# Hydrogen_Rocket_BK.net
KiCad netlist of a schematic drawn in EasyEDA
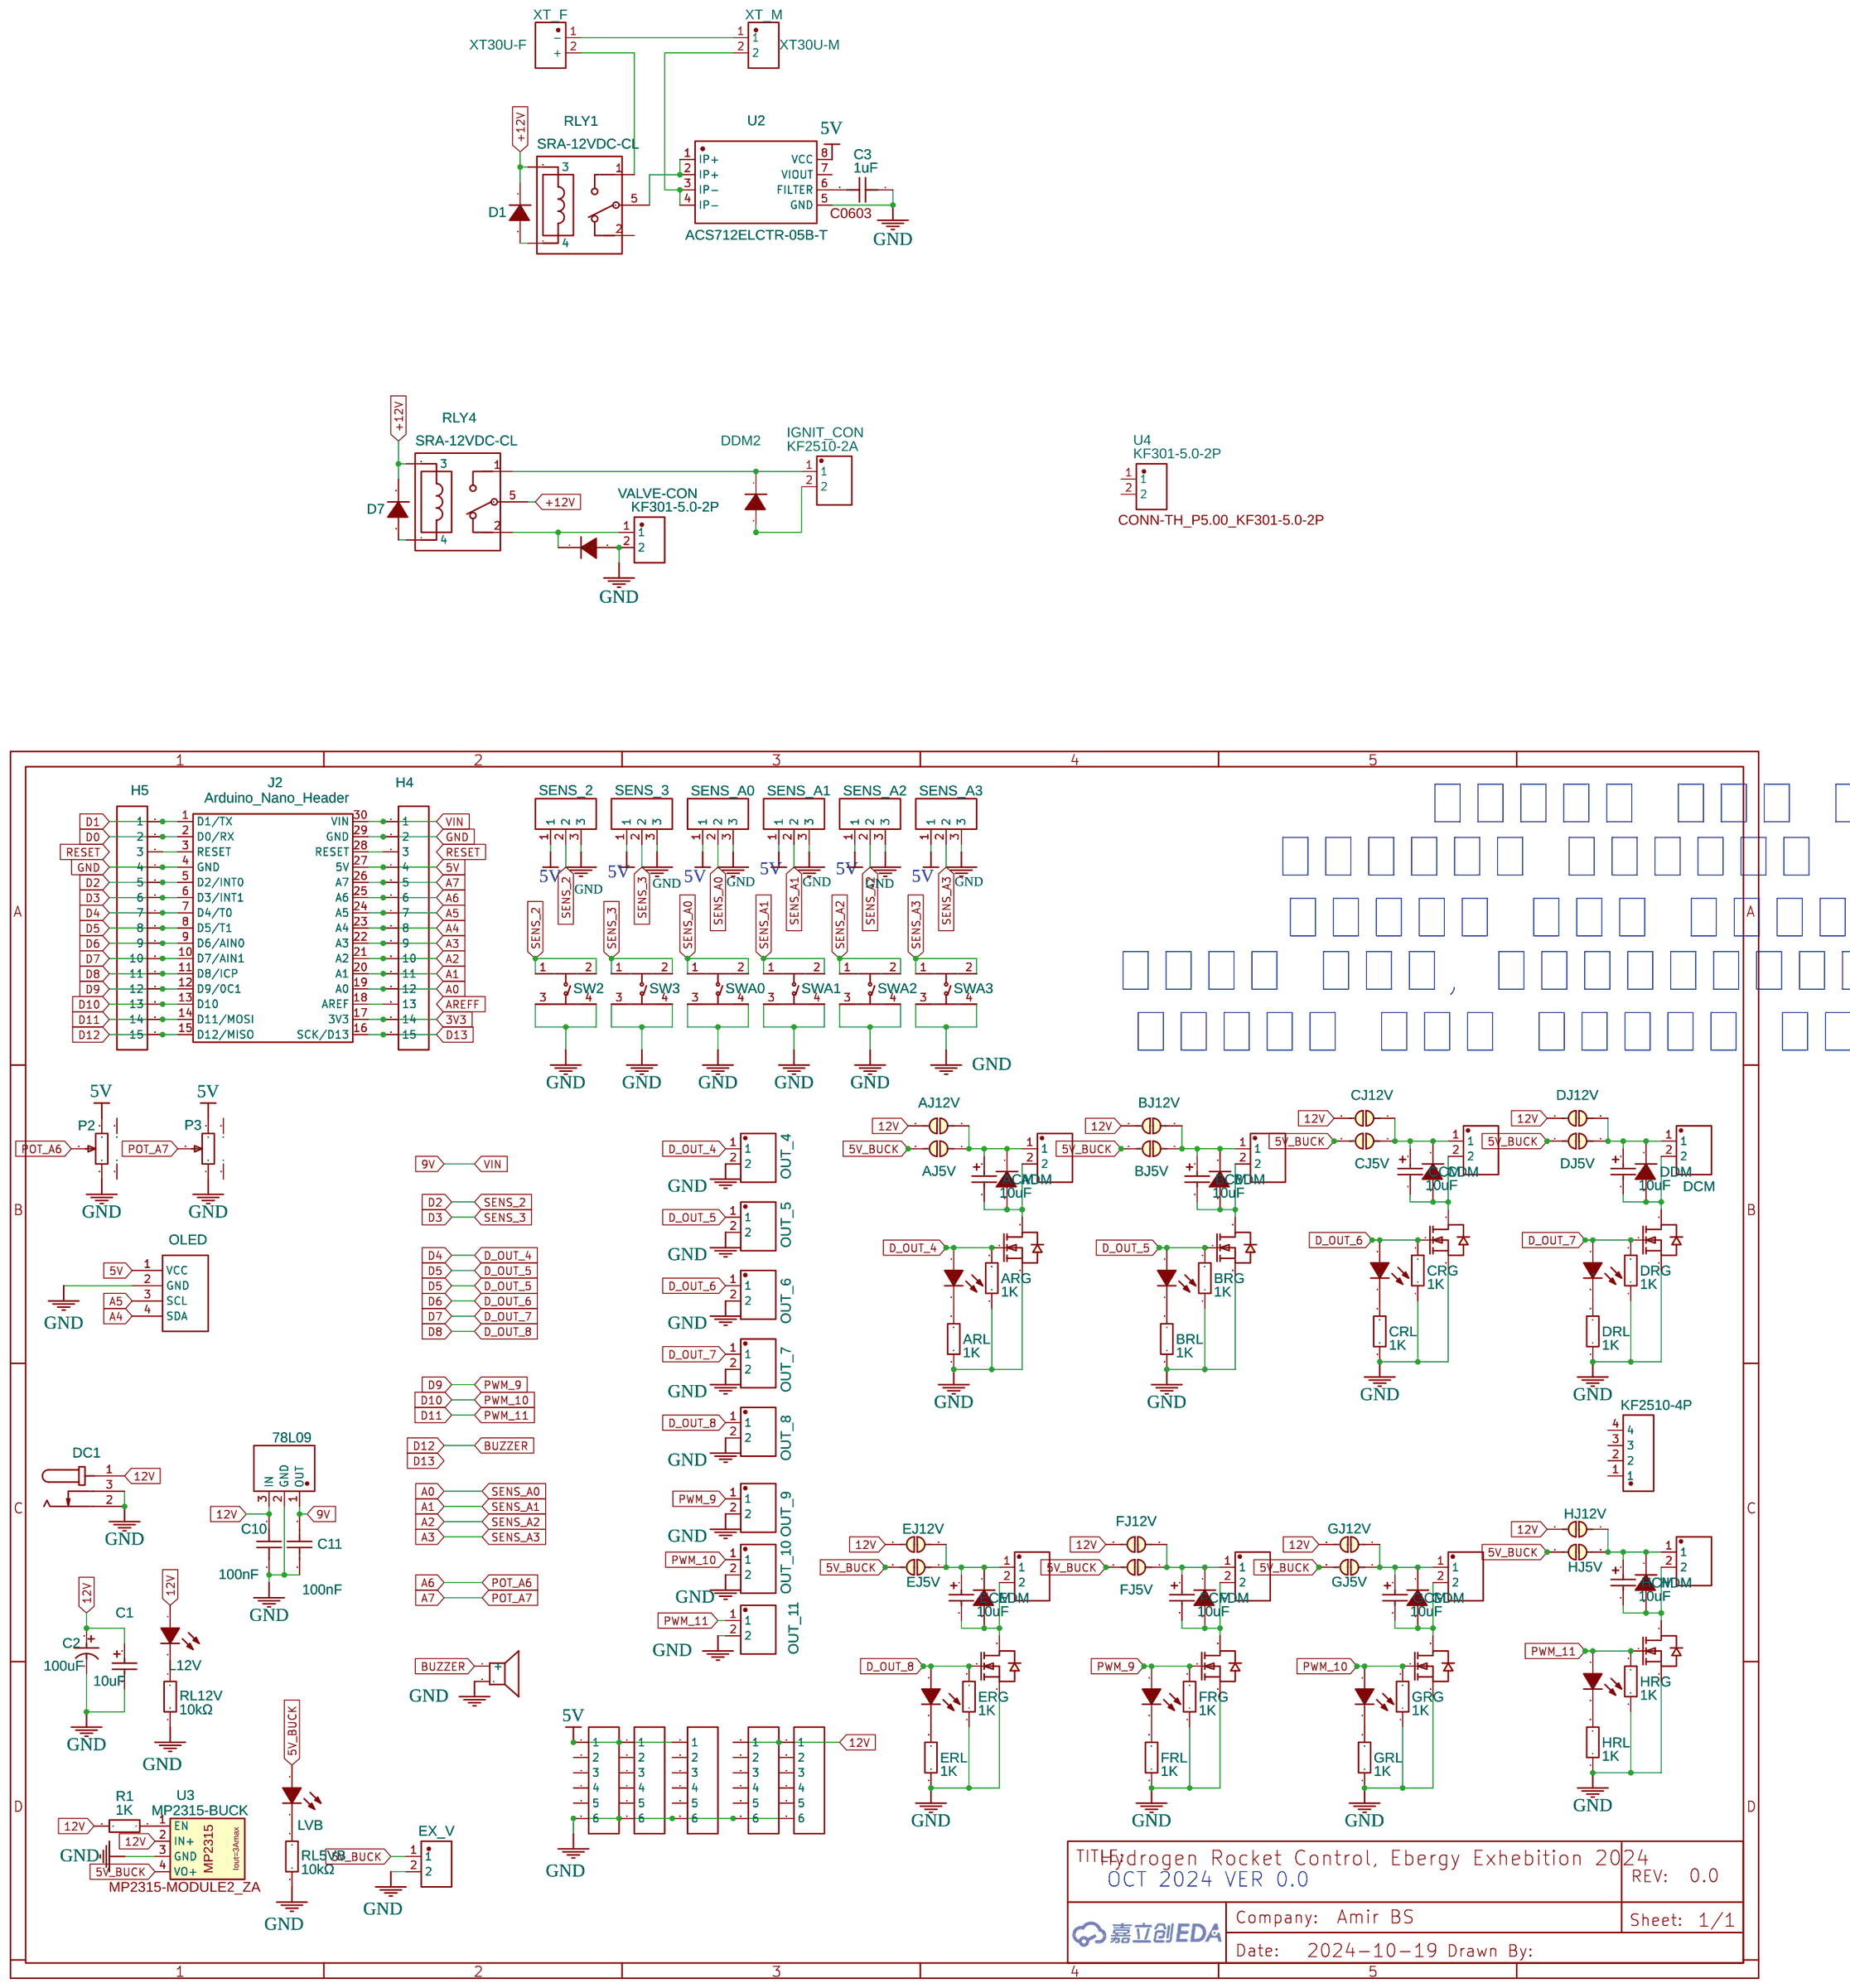
[diagram p0: schematic sheet]

(export (version "E")
  (design (tool "Eeschema 10.0.6"))
  (components
    (comp (ref "ACM")
      (value "10uF")
      (fields (field (name "Manufacturer Part") "TAJA106K016RNJ") (field (name "Manufacturer") "Kyocera AVX"))
      (libsource (lib "") (part "TAJA106K016RNJ_3"))
    )
    (comp (ref "ACON")
      (value "KF2510-2A")
      (fields (field (name "BOM_Supplier Part") "C27543"))
      (libsource (lib "") (part "KF2510-2A_9"))
    )
    (comp (ref "ADM")
      (value "1N4007")
      (fields (field (name "BOM_Manufacturer Part") "1N4007F") (field (name "BOM_Supplier Part") "C110856"))
      (libsource (lib "") (part "1N4007F_3"))
    )
    (comp (ref "AJ5V") (value "JUMPER-SMT_2") (libsource (lib "") (part "JUMPER-SMT_2_13")))
    (comp (ref "AJ12V") (value "JUMPER-SMT_2") (libsource (lib "") (part "JUMPER-SMT_2_6")))
    (comp (ref "ALD")
      (value "LED")
      (fields
        (field (name "BOM_Manufacturer Part") "19-217/BHC-ZL1M2RY/3T")
        (field (name "BOM_Supplier Part") "C72041")
      )
      (libsource (lib "") (part "19-217/BHC-ZL1M2RY/3T_6"))
    )
    (comp (ref "AQ")
      (value "Q")
      (fields (field (name "BOM_Manufacturer Part") "AO3400") (field (name "BOM_Supplier Part") "C5224189"))
      (libsource (lib "") (part "JSM2302"))
    )
    (comp (ref "ARG")
      (value "1K")
      (fields
        (field (name "BOM_Manufacturer Part") "0603WAF1001T5E")
        (field (name "BOM_Supplier Part") "C21190")
      )
      (libsource (lib "") (part "0603WAF1001T5E_7"))
    )
    (comp (ref "ARL")
      (value "1K")
      (fields
        (field (name "BOM_Manufacturer Part") "0603WAF1001T5E")
        (field (name "BOM_Supplier Part") "C21190")
      )
      (libsource (lib "") (part "0603WAF1001T5E_12"))
    )
    (comp (ref "BCM")
      (value "10uF")
      (fields (field (name "Manufacturer Part") "TAJA106K016RNJ") (field (name "Manufacturer") "Kyocera AVX"))
      (libsource (lib "") (part "TAJA106K016RNJ_2"))
    )
    (comp (ref "BCON")
      (value "KF2510-2A")
      (fields (field (name "BOM_Supplier Part") "C27543"))
      (libsource (lib "") (part "KF2510-2A"))
    )
    (comp (ref "BDM")
      (value "1N4007")
      (fields (field (name "BOM_Manufacturer Part") "1N4007F") (field (name "BOM_Supplier Part") "C110856"))
      (libsource (lib "") (part "1N4007F_8"))
    )
    (comp (ref "BJ5V") (value "JUMPER-SMT_2") (libsource (lib "") (part "JUMPER-SMT_2_1")))
    (comp (ref "BJ12V") (value "JUMPER-SMT_2") (libsource (lib "") (part "JUMPER-SMT_2")))
    (comp (ref "BLD")
      (value "LED")
      (fields
        (field (name "BOM_Manufacturer Part") "19-217/BHC-ZL1M2RY/3T")
        (field (name "BOM_Supplier Part") "C72041")
      )
      (libsource (lib "") (part "19-217/BHC-ZL1M2RY/3T_5"))
    )
    (comp (ref "BQ")
      (value "Q")
      (fields (field (name "BOM_Manufacturer Part") "AO3400") (field (name "BOM_Supplier Part") "C5224189"))
      (libsource (lib "") (part "JSM2302_2"))
    )
    (comp (ref "BRG")
      (value "1K")
      (fields
        (field (name "BOM_Manufacturer Part") "0603WAF1001T5E")
        (field (name "BOM_Supplier Part") "C21190")
      )
      (libsource (lib "") (part "0603WAF1001T5E_15"))
    )
    (comp (ref "BRL")
      (value "1K")
      (fields
        (field (name "BOM_Manufacturer Part") "0603WAF1001T5E")
        (field (name "BOM_Supplier Part") "C21190")
      )
      (libsource (lib "") (part "0603WAF1001T5E_11"))
    )
    (comp (ref "BUZZER1")
      (value "BUZZER-12X9")
      (fields (field (name "Manufacturer Part") "buzzer-12X9"))
      (libsource (lib "") (part "BUZZER-12X9"))
    )
    (comp (ref "C1")
      (value "10uF")
      (fields (field (name "Manufacturer Part") "TAJA106K016RNJ") (field (name "Manufacturer") "Kyocera AVX"))
      (libsource (lib "") (part "TAJA106K016RNJ_1"))
    )
    (comp (ref "C2")
      (value "100uF")
      (fields
        (field (name "Manufacturer Part") "KM107M035E11RR0VH2FP0")
        (field (name "Manufacturer") "CX(承兴)")
      )
      (libsource (lib "") (part "100uF 35V 6.3*11"))
    )
    (comp (ref "C3")
      (value "1uF")
      (fields
        (field (name "Manufacturer Part") "CL10A105KB8NNNC")
        (field (name "Manufacturer") "SAMSUNG(三星)")
      )
      (libsource (lib "") (part "CL10A105KB8NNNC"))
    )
    (comp (ref "C10")
      (value "100nF")
      (fields
        (field (name "Manufacturer Part") "CC0603KRX7R9BB104")
        (field (name "Manufacturer") "YAGEO(国巨)")
      )
      (libsource (lib "") (part "CC0603KRX7R9BB104"))
    )
    (comp (ref "C11")
      (value "100nF")
      (fields
        (field (name "Manufacturer Part") "CC0603KRX7R9BB104")
        (field (name "Manufacturer") "YAGEO(国巨)")
      )
      (libsource (lib "") (part "CC0603KRX7R9BB104"))
    )
    (comp (ref "CCM")
      (value "10uF")
      (fields (field (name "Manufacturer Part") "TAJA106K016RNJ") (field (name "Manufacturer") "Kyocera AVX"))
      (libsource (lib "") (part "TAJA106K016RNJ_8"))
    )
    (comp (ref "CCON")
      (value "KF2510-2A")
      (fields (field (name "BOM_Supplier Part") "C27543"))
      (libsource (lib "") (part "KF2510-2A_3"))
    )
    (comp (ref "CDM")
      (value "1N4007")
      (fields (field (name "BOM_Manufacturer Part") "1N4007F") (field (name "BOM_Supplier Part") "C110856"))
      (libsource (lib "") (part "1N4007F_2"))
    )
    (comp (ref "CJ5V") (value "JUMPER-SMT_2") (libsource (lib "") (part "JUMPER-SMT_2_4")))
    (comp (ref "CJ12V") (value "JUMPER-SMT_2") (libsource (lib "") (part "JUMPER-SMT_2_11")))
    (comp (ref "CLD")
      (value "LED")
      (fields
        (field (name "BOM_Manufacturer Part") "19-217/BHC-ZL1M2RY/3T")
        (field (name "BOM_Supplier Part") "C72041")
      )
      (libsource (lib "") (part "19-217/BHC-ZL1M2RY/3T_8"))
    )
    (comp (ref "CQ")
      (value "Q")
      (fields (field (name "BOM_Manufacturer Part") "AO3400") (field (name "BOM_Supplier Part") "C5224189"))
      (libsource (lib "") (part "JSM2302_7"))
    )
    (comp (ref "CRG")
      (value "1K")
      (fields
        (field (name "BOM_Manufacturer Part") "0603WAF1001T5E")
        (field (name "BOM_Supplier Part") "C21190")
      )
      (libsource (lib "") (part "0603WAF1001T5E"))
    )
    (comp (ref "CRL")
      (value "1K")
      (fields
        (field (name "BOM_Manufacturer Part") "0603WAF1001T5E")
        (field (name "BOM_Supplier Part") "C21190")
      )
      (libsource (lib "") (part "0603WAF1001T5E_8"))
    )
    (comp (ref "D1")
      (value "M7_C95872")
      (fields (field (name "Manufacturer Part") "M7") (field (name "Manufacturer") "MDD"))
      (libsource (lib "") (part "M7_C95872"))
    )
    (comp (ref "D7")
      (value "M7_C95872")
      (fields (field (name "Manufacturer Part") "M7") (field (name "Manufacturer") "MDD"))
      (libsource (lib "") (part "M7_C95872"))
    )
    (comp (ref "DC1")
      (value "DC")
      (fields
        (field (name "BOM_Manufacturer Part") "DC005-2.0MM")
        (field (name "BOM_Supplier Part") "C111567")
      )
      (libsource (lib "") (part "DC005-2.0MM"))
    )
    (comp (ref "DCM")
      (value "10uF")
      (fields (field (name "Manufacturer Part") "TAJA106K016RNJ") (field (name "Manufacturer") "Kyocera AVX"))
      (libsource (lib "") (part "TAJA106K016RNJ_5"))
    )
    (comp (ref "DCON")
      (value "KF2510-2A")
      (fields (field (name "BOM_Supplier Part") "C27543"))
      (libsource (lib "") (part "KF2510-2A_2"))
    )
    (comp (ref "DDM")
      (value "1N4007")
      (fields (field (name "BOM_Manufacturer Part") "1N4007F") (field (name "BOM_Supplier Part") "C110856"))
      (libsource (lib "") (part "1N4007F_6"))
    )
    (comp (ref "DDM1")
      (value "1N4007")
      (fields (field (name "BOM_Manufacturer Part") "1N4007F") (field (name "BOM_Supplier Part") "C110856"))
      (libsource (lib "") (part "1N4007F_1"))
    )
    (comp (ref "DDM2")
      (value "1N4007")
      (fields (field (name "BOM_Manufacturer Part") "1N4007F") (field (name "BOM_Supplier Part") "C110856"))
      (libsource (lib "") (part "1N4007F_6"))
    )
    (comp (ref "DJ5V") (value "JUMPER-SMT_2") (libsource (lib "") (part "JUMPER-SMT_2_15")))
    (comp (ref "DJ12V") (value "JUMPER-SMT_2") (libsource (lib "") (part "JUMPER-SMT_2_2")))
    (comp (ref "DLD")
      (value "LED")
      (fields
        (field (name "BOM_Manufacturer Part") "19-217/BHC-ZL1M2RY/3T")
        (field (name "BOM_Supplier Part") "C72041")
      )
      (libsource (lib "") (part "19-217/BHC-ZL1M2RY/3T_7"))
    )
    (comp (ref "DQ")
      (value "Q")
      (fields (field (name "BOM_Manufacturer Part") "AO3400") (field (name "BOM_Supplier Part") "C5224189"))
      (libsource (lib "") (part "JSM2302_6"))
    )
    (comp (ref "DRG")
      (value "1K")
      (fields
        (field (name "BOM_Manufacturer Part") "0603WAF1001T5E")
        (field (name "BOM_Supplier Part") "C21190")
      )
      (libsource (lib "") (part "0603WAF1001T5E_4"))
    )
    (comp (ref "DRL")
      (value "1K")
      (fields
        (field (name "BOM_Manufacturer Part") "0603WAF1001T5E")
        (field (name "BOM_Supplier Part") "C21190")
      )
      (libsource (lib "") (part "0603WAF1001T5E_14"))
    )
    (comp (ref "ECM")
      (value "10uF")
      (fields (field (name "Manufacturer Part") "TAJA106K016RNJ") (field (name "Manufacturer") "Kyocera AVX"))
      (libsource (lib "") (part "TAJA106K016RNJ_7"))
    )
    (comp (ref "ECON")
      (value "KF2510-2A")
      (fields (field (name "BOM_Supplier Part") "C27543"))
      (libsource (lib "") (part "KF2510-2A_4"))
    )
    (comp (ref "EDM")
      (value "1N4007")
      (fields (field (name "BOM_Manufacturer Part") "1N4007F") (field (name "BOM_Supplier Part") "C110856"))
      (libsource (lib "") (part "1N4007F"))
    )
    (comp (ref "EJ5V") (value "JUMPER-SMT_2") (libsource (lib "") (part "JUMPER-SMT_2_14")))
    (comp (ref "EJ12V") (value "JUMPER-SMT_2") (libsource (lib "") (part "JUMPER-SMT_2_12")))
    (comp (ref "ELD")
      (value "LED")
      (fields
        (field (name "BOM_Manufacturer Part") "19-217/BHC-ZL1M2RY/3T")
        (field (name "BOM_Supplier Part") "C72041")
      )
      (libsource (lib "") (part "19-217/BHC-ZL1M2RY/3T_3"))
    )
    (comp (ref "EQ")
      (value "Q")
      (fields (field (name "BOM_Manufacturer Part") "AO3400") (field (name "BOM_Supplier Part") "C5224189"))
      (libsource (lib "") (part "JSM2302_4"))
    )
    (comp (ref "ERG")
      (value "1K")
      (fields
        (field (name "BOM_Manufacturer Part") "0603WAF1001T5E")
        (field (name "BOM_Supplier Part") "C21190")
      )
      (libsource (lib "") (part "0603WAF1001T5E_9"))
    )
    (comp (ref "ERL")
      (value "1K")
      (fields
        (field (name "BOM_Manufacturer Part") "0603WAF1001T5E")
        (field (name "BOM_Supplier Part") "C21190")
      )
      (libsource (lib "") (part "0603WAF1001T5E_5"))
    )
    (comp (ref "EX_V")
      (value "EX_V")
      (fields
        (field (name "Manufacturer Part") "WJ306V-5.0-2P-14-00A")
        (field (name "Manufacturer") "KANGNEX(康奈克斯电气)")
      )
      (libsource (lib "") (part "WJ306V-5.0-2P-14-00A"))
    )
    (comp (ref "FCM")
      (value "10uF")
      (fields (field (name "Manufacturer Part") "TAJA106K016RNJ") (field (name "Manufacturer") "Kyocera AVX"))
      (libsource (lib "") (part "TAJA106K016RNJ"))
    )
    (comp (ref "FCON")
      (value "KF2510-2A")
      (fields (field (name "BOM_Supplier Part") "C27543"))
      (libsource (lib "") (part "KF2510-2A_8"))
    )
    (comp (ref "FDM")
      (value "1N4007")
      (fields (field (name "BOM_Manufacturer Part") "1N4007F") (field (name "BOM_Supplier Part") "C110856"))
      (libsource (lib "") (part "1N4007F_4"))
    )
    (comp (ref "FJ5V") (value "JUMPER-SMT_2") (libsource (lib "") (part "JUMPER-SMT_2_5")))
    (comp (ref "FJ12V") (value "JUMPER-SMT_2") (libsource (lib "") (part "JUMPER-SMT_2_10")))
    (comp (ref "FLD")
      (value "LED")
      (fields
        (field (name "BOM_Manufacturer Part") "19-217/BHC-ZL1M2RY/3T")
        (field (name "BOM_Supplier Part") "C72041")
      )
      (libsource (lib "") (part "19-217/BHC-ZL1M2RY/3T"))
    )
    (comp (ref "FQ")
      (value "Q")
      (fields (field (name "BOM_Manufacturer Part") "AO3400") (field (name "BOM_Supplier Part") "C5224189"))
      (libsource (lib "") (part "JSM2302_1"))
    )
    (comp (ref "FRG")
      (value "1K")
      (fields
        (field (name "BOM_Manufacturer Part") "0603WAF1001T5E")
        (field (name "BOM_Supplier Part") "C21190")
      )
      (libsource (lib "") (part "0603WAF1001T5E_10"))
    )
    (comp (ref "FRL")
      (value "1K")
      (fields
        (field (name "BOM_Manufacturer Part") "0603WAF1001T5E")
        (field (name "BOM_Supplier Part") "C21190")
      )
      (libsource (lib "") (part "0603WAF1001T5E_16"))
    )
    (comp (ref "GCM")
      (value "10uF")
      (fields (field (name "Manufacturer Part") "TAJA106K016RNJ") (field (name "Manufacturer") "Kyocera AVX"))
      (libsource (lib "") (part "TAJA106K016RNJ_6"))
    )
    (comp (ref "GCON")
      (value "KF2510-2A")
      (fields (field (name "BOM_Supplier Part") "C27543"))
      (libsource (lib "") (part "KF2510-2A_7"))
    )
    (comp (ref "GDM")
      (value "1N4007")
      (fields (field (name "BOM_Manufacturer Part") "1N4007F") (field (name "BOM_Supplier Part") "C110856"))
      (libsource (lib "") (part "1N4007F_7"))
    )
    (comp (ref "GJ5V") (value "JUMPER-SMT_2") (libsource (lib "") (part "JUMPER-SMT_2_9")))
    (comp (ref "GJ12V") (value "JUMPER-SMT_2") (libsource (lib "") (part "JUMPER-SMT_2_3")))
    (comp (ref "GLD")
      (value "LED")
      (fields
        (field (name "BOM_Manufacturer Part") "19-217/BHC-ZL1M2RY/3T")
        (field (name "BOM_Supplier Part") "C72041")
      )
      (libsource (lib "") (part "19-217/BHC-ZL1M2RY/3T_9"))
    )
    (comp (ref "GQ")
      (value "Q")
      (fields (field (name "BOM_Manufacturer Part") "AO3400") (field (name "BOM_Supplier Part") "C5224189"))
      (libsource (lib "") (part "JSM2302_5"))
    )
    (comp (ref "GRG")
      (value "1K")
      (fields
        (field (name "BOM_Manufacturer Part") "0603WAF1001T5E")
        (field (name "BOM_Supplier Part") "C21190")
      )
      (libsource (lib "") (part "0603WAF1001T5E_3"))
    )
    (comp (ref "GRL")
      (value "1K")
      (fields
        (field (name "BOM_Manufacturer Part") "0603WAF1001T5E")
        (field (name "BOM_Supplier Part") "C21190")
      )
      (libsource (lib "") (part "0603WAF1001T5E_13"))
    )
    (comp (ref "H1")
      (value "HDR-F-2.54_1x6")
      (fields (field (name "BOM_Supplier Part") "C40877"))
      (libsource (lib "") (part "HDR-F-2.54_1x6"))
    )
    (comp (ref "H2")
      (value "HDR-F-2.54_1x6")
      (fields (field (name "BOM_Supplier Part") "C40877"))
      (libsource (lib "") (part "HDR-F-2.54_1x6"))
    )
    (comp (ref "H3")
      (value "HDR-F-2.54_1x6")
      (fields (field (name "BOM_Supplier Part") "C40877"))
      (libsource (lib "") (part "HDR-F-2.54_1x6"))
    )
    (comp (ref "H4")
      (value "HDR-F-2.54_1x15")
      (fields (field (name "BOM_Supplier Part") "C124408"))
      (libsource (lib "") (part "HDR-F-2.54_1x15_1"))
    )
    (comp (ref "H5")
      (value "HDR-F-2.54_1x15")
      (fields (field (name "BOM_Supplier Part") "C124408"))
      (libsource (lib "") (part "HDR-F-2.54_1x15"))
    )
    (comp (ref "H6")
      (value "HDR-F-2.54_1x6")
      (fields (field (name "BOM_Supplier Part") "C40877"))
      (libsource (lib "") (part "HDR-F-2.54_1x6"))
    )
    (comp (ref "H11")
      (value "HDR-F-2.54_1x6")
      (fields (field (name "BOM_Supplier Part") "C40877"))
      (libsource (lib "") (part "HDR-F-2.54_1x6"))
    )
    (comp (ref "HCM")
      (value "10uF")
      (fields (field (name "Manufacturer Part") "TAJA106K016RNJ") (field (name "Manufacturer") "Kyocera AVX"))
      (libsource (lib "") (part "TAJA106K016RNJ_4"))
    )
    (comp (ref "HCON")
      (value "KF2510-2A")
      (fields (field (name "BOM_Supplier Part") "C27543"))
      (libsource (lib "") (part "KF2510-2A_5"))
    )
    (comp (ref "HDM")
      (value "1N4007")
      (fields (field (name "BOM_Manufacturer Part") "1N4007F") (field (name "BOM_Supplier Part") "C110856"))
      (libsource (lib "") (part "1N4007F_5"))
    )
    (comp (ref "HJ5V") (value "JUMPER-SMT_2") (libsource (lib "") (part "JUMPER-SMT_2_7")))
    (comp (ref "HJ12V") (value "JUMPER-SMT_2") (libsource (lib "") (part "JUMPER-SMT_2_8")))
    (comp (ref "HLD")
      (value "LED")
      (fields
        (field (name "BOM_Manufacturer Part") "19-217/BHC-ZL1M2RY/3T")
        (field (name "BOM_Supplier Part") "C72041")
      )
      (libsource (lib "") (part "19-217/BHC-ZL1M2RY/3T_1"))
    )
    (comp (ref "HQ")
      (value "Q")
      (fields (field (name "BOM_Manufacturer Part") "AO3400") (field (name "BOM_Supplier Part") "C5224189"))
      (libsource (lib "") (part "JSM2302_3"))
    )
    (comp (ref "HRG")
      (value "1K")
      (fields
        (field (name "BOM_Manufacturer Part") "0603WAF1001T5E")
        (field (name "BOM_Supplier Part") "C21190")
      )
      (libsource (lib "") (part "0603WAF1001T5E_2"))
    )
    (comp (ref "HRL")
      (value "1K")
      (fields
        (field (name "BOM_Manufacturer Part") "0603WAF1001T5E")
        (field (name "BOM_Supplier Part") "C21190")
      )
      (libsource (lib "") (part "0603WAF1001T5E_1"))
    )
    (comp (ref "IGNIT_CON")
      (value "KF2510-2A")
      (fields (field (name "BOM_Supplier Part") "C27543"))
      (libsource (lib "") (part "KF2510-2A_1"))
    )
    (comp (ref "J2") (value "Arduino_Nano_Header") (libsource (lib "") (part "Arduino_Nano_Header")))
    (comp (ref "L12V")
      (value "LED")
      (fields
        (field (name "BOM_Manufacturer Part") "19-217/BHC-ZL1M2RY/3T")
        (field (name "BOM_Supplier Part") "C72041")
      )
      (libsource (lib "") (part "19-217/BHC-ZL1M2RY/3T_4"))
    )
    (comp (ref "LVB")
      (value "LED")
      (fields
        (field (name "BOM_Manufacturer Part") "19-217/BHC-ZL1M2RY/3T")
        (field (name "BOM_Supplier Part") "C72041")
      )
      (libsource (lib "") (part "19-217/BHC-ZL1M2RY/3T_2"))
    )
    (comp (ref "OLED")
      (value "1.3 inch OLED SSH1106 I2C 128x64 copy")
      (libsource (lib "") (part "1.3 inch OLED SSH1106 I2C 128x64 copy"))
    )
    (comp (ref "OUT_4")
      (value "KF2510-2A")
      (fields (field (name "BOM_Supplier Part") "C27543"))
      (libsource (lib "") (part "KF2510-2A_6"))
    )
    (comp (ref "OUT_5")
      (value "KF2510-2A")
      (fields (field (name "BOM_Supplier Part") "C27543"))
      (libsource (lib "") (part "KF2510-2A_6"))
    )
    (comp (ref "OUT_6")
      (value "KF2510-2A")
      (fields (field (name "BOM_Supplier Part") "C27543"))
      (libsource (lib "") (part "KF2510-2A_6"))
    )
    (comp (ref "OUT_7")
      (value "KF2510-2A")
      (fields (field (name "BOM_Supplier Part") "C27543"))
      (libsource (lib "") (part "KF2510-2A_6"))
    )
    (comp (ref "OUT_8")
      (value "KF2510-2A")
      (fields (field (name "BOM_Supplier Part") "C27543"))
      (libsource (lib "") (part "KF2510-2A_6"))
    )
    (comp (ref "OUT_9")
      (value "KF2510-2A")
      (fields (field (name "BOM_Supplier Part") "C27543"))
      (libsource (lib "") (part "KF2510-2A_6"))
    )
    (comp (ref "OUT_10")
      (value "KF2510-2A")
      (fields (field (name "BOM_Supplier Part") "C27543"))
      (libsource (lib "") (part "KF2510-2A_6"))
    )
    (comp (ref "OUT_11")
      (value "KF2510-2A")
      (fields (field (name "BOM_Supplier Part") "C27543"))
      (libsource (lib "") (part "KF2510-2A_6"))
    )
    (comp (ref "P2")
      (value "长柄旋转电位器")
      (fields (field (name "BOM_Supplier Part") "C2874842"))
      (libsource (lib "") (part "长柄旋转电位器"))
    )
    (comp (ref "P3")
      (value "长柄旋转电位器")
      (fields (field (name "BOM_Supplier Part") "C2874842"))
      (libsource (lib "") (part "长柄旋转电位器"))
    )
    (comp (ref "R1")
      (value "1K")
      (fields
        (field (name "BOM_Manufacturer Part") "0603WAF1001T5E")
        (field (name "BOM_Supplier Part") "C21190")
      )
      (libsource (lib "") (part "0603WAF1001T5E_6"))
    )
    (comp (ref "RL5VB")
      (value "10kΩ")
      (fields
        (field (name "BOM_Manufacturer Part") "0603WAF1002T5E")
        (field (name "BOM_Supplier Part") "C25804")
      )
      (libsource (lib "") (part "0603WAF1002T5E_1"))
    )
    (comp (ref "RL12V")
      (value "10kΩ")
      (fields
        (field (name "BOM_Manufacturer Part") "0603WAF1002T5E")
        (field (name "BOM_Supplier Part") "C25804")
      )
      (libsource (lib "") (part "0603WAF1002T5E"))
    )
    (comp (ref "RLY1")
      (value "SRA-12VDC-CL")
      (fields (field (name "Manufacturer") "松乐"))
      (libsource (lib "") (part "SRA-12VDC-CL"))
    )
    (comp (ref "RLY4")
      (value "SRA-12VDC-CL")
      (fields (field (name "Manufacturer") "松乐"))
      (libsource (lib "") (part "SRA-12VDC-CL"))
    )
    (comp (ref "SENS_2")
      (value "FK2510")
      (fields (field (name "Manufacturer Part") "2510-3A") (field (name "Manufacturer") "BOOMELE(博穆精密)"))
      (libsource (lib "") (part "kf2510_3A_1"))
    )
    (comp (ref "SENS_3")
      (value "FK2510")
      (fields (field (name "Manufacturer Part") "2510-3A") (field (name "Manufacturer") "BOOMELE(博穆精密)"))
      (libsource (lib "") (part "kf2510_3A_1"))
    )
    (comp (ref "SENS_A0")
      (value "FK2510")
      (fields (field (name "Manufacturer Part") "2510-3A") (field (name "Manufacturer") "BOOMELE(博穆精密)"))
      (libsource (lib "") (part "kf2510_3A"))
    )
    (comp (ref "SENS_A1")
      (value "FK2510")
      (fields (field (name "Manufacturer Part") "2510-3A") (field (name "Manufacturer") "BOOMELE(博穆精密)"))
      (libsource (lib "") (part "kf2510_3A"))
    )
    (comp (ref "SENS_A2")
      (value "FK2510")
      (fields (field (name "Manufacturer Part") "2510-3A") (field (name "Manufacturer") "BOOMELE(博穆精密)"))
      (libsource (lib "") (part "kf2510_3A"))
    )
    (comp (ref "SENS_A3")
      (value "FK2510")
      (fields (field (name "Manufacturer Part") "2510-3A") (field (name "Manufacturer") "BOOMELE(博穆精密)"))
      (libsource (lib "") (part "kf2510_3A"))
    )
    (comp (ref "SW2")
      (value "TC-6610-7-160G")
      (fields (field (name "Manufacturer") "HCTL(华灿天禄)"))
      (libsource (lib "") (part "TC-6610-7-160G"))
    )
    (comp (ref "SW3")
      (value "TC-6610-7-160G")
      (fields (field (name "Manufacturer") "HCTL(华灿天禄)"))
      (libsource (lib "") (part "TC-6610-7-160G"))
    )
    (comp (ref "SWA0")
      (value "TC-6610-7-160G")
      (fields (field (name "Manufacturer") "HCTL(华灿天禄)"))
      (libsource (lib "") (part "TC-6610-7-160G_1"))
    )
    (comp (ref "SWA1")
      (value "TC-6610-7-160G")
      (fields (field (name "Manufacturer") "HCTL(华灿天禄)"))
      (libsource (lib "") (part "TC-6610-7-160G_1"))
    )
    (comp (ref "SWA2")
      (value "TC-6610-7-160G")
      (fields (field (name "Manufacturer") "HCTL(华灿天禄)"))
      (libsource (lib "") (part "TC-6610-7-160G_1"))
    )
    (comp (ref "SWA3")
      (value "TC-6610-7-160G")
      (fields (field (name "Manufacturer") "HCTL(华灿天禄)"))
      (libsource (lib "") (part "TC-6610-7-160G_1"))
    )
    (comp (ref "U1")
      (value "KF2510-4P")
      (fields (field (name "BOM_Supplier Part") "C9900008392"))
      (libsource (lib "") (part "KF2510-4P"))
    )
    (comp (ref "U2")
      (value "ACS712ELCTR-05B-T")
      (fields (field (name "Manufacturer") "ALLEGRO(美国埃戈罗)"))
      (libsource (lib "") (part "ACS712ELCTR-05B-T"))
    )
    (comp (ref "U3") (value "MP2315-BUCK") (libsource (lib "") (part "MP2315-BUCK")))
    (comp (ref "U4")
      (value "KF301-5.0-2P")
      (fields (field (name "Manufacturer") "KEFA(科发)"))
      (libsource (lib "") (part "KF301-5.0-2P"))
    )
    (comp (ref "U5")
      (value "78L09")
      (fields (field (name "Manufacturer Part") "78L09U 78L09") (field (name "Manufacturer") "CBI(创基)"))
      (libsource (lib "") (part "78L09U 78L09"))
    )
    (comp (ref "VALVE-CON")
      (value "KF301-5.0-2P")
      (fields (field (name "Manufacturer") "KEFA(科发)"))
      (libsource (lib "") (part "KF301-5.0-2P_1"))
    )
    (comp (ref "XT_F")
      (value "XT30U-F")
      (fields (field (name "Manufacturer") "AMASS(艾迈斯)"))
      (libsource (lib "") (part "XT30U-F"))
    )
    (comp (ref "XT_M")
      (value "XT30U-M")
      (fields (field (name "Manufacturer") "AMASS(艾迈斯)"))
      (libsource (lib "") (part "XT30U-M"))
    )
  )
  (nets
    (net (code "1") (name "+12V") (class "Default")
      (node (ref "D1") (pin "1") (pinfunction "K_1") (pintype "unspecified"))
      (node (ref "D7") (pin "1") (pinfunction "K_1") (pintype "unspecified"))
      (node (ref "RLY1") (pin "3") (pinfunction "3_3") (pintype "unspecified"))
      (node (ref "RLY4") (pin "3") (pinfunction "3_3") (pintype "unspecified"))
      (node (ref "RLY4") (pin "5") (pinfunction "5_5") (pintype "unspecified"))
    )
    (net (code "2") (name "3V3") (class "Default")
      (node (ref "H4") (pin "14") (pinfunction "14_14") (pintype "unspecified"))
      (node (ref "J2") (pin "17") (pinfunction "3V3_17") (pintype "unspecified"))
    )
    (net (code "3") (name "5V") (class "Default")
      (node (ref "H1") (pin "1") (pinfunction "1_1") (pintype "input"))
      (node (ref "H2") (pin "1") (pinfunction "1_1") (pintype "input"))
      (node (ref "H3") (pin "1") (pinfunction "1_1") (pintype "input"))
      (node (ref "H4") (pin "4") (pinfunction "4_4") (pintype "unspecified"))
      (node (ref "J2") (pin "27") (pinfunction "5V_27") (pintype "unspecified"))
      (node (ref "OLED") (pin "1") (pinfunction "VCC_1") (pintype "passive"))
      (node (ref "P2") (pin "3") (pinfunction "3_3") (pintype "input"))
      (node (ref "P3") (pin "3") (pinfunction "3_3") (pintype "input"))
      (node (ref "SENS_2") (pin "1") (pinfunction "1_1") (pintype "unspecified"))
      (node (ref "SENS_3") (pin "1") (pinfunction "1_1") (pintype "unspecified"))
      (node (ref "SENS_A0") (pin "1") (pinfunction "1_1") (pintype "unspecified"))
      (node (ref "SENS_A1") (pin "1") (pinfunction "1_1") (pintype "unspecified"))
      (node (ref "SENS_A2") (pin "1") (pinfunction "1_1") (pintype "unspecified"))
      (node (ref "SENS_A3") (pin "1") (pinfunction "1_1") (pintype "unspecified"))
      (node (ref "U2") (pin "8") (pinfunction "VCC_8") (pintype "unspecified"))
    )
    (net (code "4") (name "5V_BUCK") (class "Default")
      (node (ref "AJ5V") (pin "2") (pinfunction "2_2") (pintype "bidirectional"))
      (node (ref "BJ5V") (pin "2") (pinfunction "2_2") (pintype "bidirectional"))
      (node (ref "CJ5V") (pin "2") (pinfunction "2_2") (pintype "bidirectional"))
      (node (ref "DJ5V") (pin "2") (pinfunction "2_2") (pintype "bidirectional"))
      (node (ref "EJ5V") (pin "2") (pinfunction "2_2") (pintype "bidirectional"))
      (node (ref "EX_V") (pin "1") (pinfunction "1_1") (pintype "unspecified"))
      (node (ref "FJ5V") (pin "2") (pinfunction "2_2") (pintype "bidirectional"))
      (node (ref "GJ5V") (pin "2") (pinfunction "2_2") (pintype "bidirectional"))
      (node (ref "HJ5V") (pin "2") (pinfunction "2_2") (pintype "bidirectional"))
      (node (ref "LVB") (pin "1") (pinfunction "A_1") (pintype "input"))
      (node (ref "U3") (pin "4") (pinfunction "VO+_4") (pintype "unspecified"))
    )
    (net (code "5") (name "9V") (class "Default")
      (node (ref "C11") (pin "2") (pinfunction "2_2") (pintype "unspecified"))
      (node (ref "H4") (pin "1") (pinfunction "1_1") (pintype "unspecified"))
      (node (ref "J2") (pin "30") (pinfunction "VIN_30") (pintype "unspecified"))
      (node (ref "U5") (pin "1") (pinfunction "OUT_1") (pintype "unspecified"))
    )
    (net (code "6") (name "12V") (class "Default")
      (node (ref "AJ12V") (pin "2") (pinfunction "2_2") (pintype "bidirectional"))
      (node (ref "BJ12V") (pin "2") (pinfunction "2_2") (pintype "bidirectional"))
      (node (ref "C1") (pin "1") (pinfunction "1_1") (pintype "input"))
      (node (ref "C10") (pin "2") (pinfunction "2_2") (pintype "unspecified"))
      (node (ref "C2") (pin "1") (pinfunction "1_1") (pintype "input"))
      (node (ref "CJ12V") (pin "2") (pinfunction "2_2") (pintype "bidirectional"))
      (node (ref "DC1") (pin "1") (pinfunction "1_1") (pintype "unspecified"))
      (node (ref "DJ12V") (pin "2") (pinfunction "2_2") (pintype "bidirectional"))
      (node (ref "EJ12V") (pin "2") (pinfunction "2_2") (pintype "bidirectional"))
      (node (ref "FJ12V") (pin "2") (pinfunction "2_2") (pintype "bidirectional"))
      (node (ref "GJ12V") (pin "2") (pinfunction "2_2") (pintype "bidirectional"))
      (node (ref "H11") (pin "1") (pinfunction "1_1") (pintype "input"))
      (node (ref "H6") (pin "1") (pinfunction "1_1") (pintype "input"))
      (node (ref "HJ12V") (pin "2") (pinfunction "2_2") (pintype "bidirectional"))
      (node (ref "L12V") (pin "1") (pinfunction "A_1") (pintype "input"))
      (node (ref "R1") (pin "2") (pinfunction "2_2") (pintype "input"))
      (node (ref "U3") (pin "2") (pinfunction "IN+_2") (pintype "unspecified"))
      (node (ref "U5") (pin "3") (pinfunction "IN_3") (pintype "unspecified"))
    )
    (net (code "7") (name "A0") (class "Default")
      (node (ref "H4") (pin "12") (pinfunction "12_12") (pintype "unspecified"))
      (node (ref "J2") (pin "19") (pinfunction "A0_19") (pintype "unspecified"))
      (node (ref "SENS_A0") (pin "2") (pinfunction "2_2") (pintype "unspecified"))
      (node (ref "SWA0") (pin "1") (pinfunction "1_1") (pintype "unspecified"))
      (node (ref "SWA0") (pin "2") (pinfunction "2_2") (pintype "unspecified"))
    )
    (net (code "8") (name "A1") (class "Default")
      (node (ref "H4") (pin "11") (pinfunction "11_11") (pintype "unspecified"))
      (node (ref "J2") (pin "20") (pinfunction "A1_20") (pintype "unspecified"))
      (node (ref "SENS_A1") (pin "2") (pinfunction "2_2") (pintype "unspecified"))
      (node (ref "SWA1") (pin "1") (pinfunction "1_1") (pintype "unspecified"))
      (node (ref "SWA1") (pin "2") (pinfunction "2_2") (pintype "unspecified"))
    )
    (net (code "9") (name "A2") (class "Default")
      (node (ref "H4") (pin "10") (pinfunction "10_10") (pintype "unspecified"))
      (node (ref "J2") (pin "21") (pinfunction "A2_21") (pintype "unspecified"))
      (node (ref "SENS_A2") (pin "2") (pinfunction "2_2") (pintype "unspecified"))
      (node (ref "SWA2") (pin "1") (pinfunction "1_1") (pintype "unspecified"))
      (node (ref "SWA2") (pin "2") (pinfunction "2_2") (pintype "unspecified"))
    )
    (net (code "10") (name "A3") (class "Default")
      (node (ref "H4") (pin "9") (pinfunction "9_9") (pintype "unspecified"))
      (node (ref "J2") (pin "22") (pinfunction "A3_22") (pintype "unspecified"))
      (node (ref "SENS_A3") (pin "2") (pinfunction "2_2") (pintype "unspecified"))
      (node (ref "SWA3") (pin "1") (pinfunction "1_1") (pintype "unspecified"))
      (node (ref "SWA3") (pin "2") (pinfunction "2_2") (pintype "unspecified"))
    )
    (net (code "11") (name "A4") (class "Default")
      (node (ref "H4") (pin "8") (pinfunction "8_8") (pintype "unspecified"))
      (node (ref "J2") (pin "23") (pinfunction "A4_23") (pintype "unspecified"))
      (node (ref "OLED") (pin "4") (pinfunction "SDA_4") (pintype "bidirectional"))
    )
    (net (code "12") (name "A5") (class "Default")
      (node (ref "H4") (pin "7") (pinfunction "7_7") (pintype "unspecified"))
      (node (ref "J2") (pin "24") (pinfunction "A5_24") (pintype "unspecified"))
      (node (ref "OLED") (pin "3") (pinfunction "SCL_3") (pintype "bidirectional"))
    )
    (net (code "13") (name "A6") (class "Default")
      (node (ref "H4") (pin "6") (pinfunction "6_6") (pintype "unspecified"))
      (node (ref "J2") (pin "25") (pinfunction "A6_25") (pintype "unspecified"))
      (node (ref "P2") (pin "2") (pinfunction "2_2") (pintype "input"))
    )
    (net (code "14") (name "A7") (class "Default")
      (node (ref "H4") (pin "5") (pinfunction "5_5") (pintype "unspecified"))
      (node (ref "J2") (pin "26") (pinfunction "A7_26") (pintype "unspecified"))
      (node (ref "P3") (pin "2") (pinfunction "2_2") (pintype "input"))
    )
    (net (code "16") (name "BUZZER") (class "Default")
      (node (ref "BUZZER1") (pin "1") (pinfunction "+_1") (pintype "unspecified"))
      (node (ref "H5") (pin "15") (pinfunction "15_15") (pintype "unspecified"))
      (node (ref "J2") (pin "15") (pinfunction "D12/MISO_15") (pintype "unspecified"))
    )
    (net (code "17") (name "D0") (class "Default")
      (node (ref "H5") (pin "2") (pinfunction "2_2") (pintype "unspecified"))
      (node (ref "J2") (pin "2") (pinfunction "D0/RX_2") (pintype "unspecified"))
    )
    (net (code "18") (name "D1") (class "Default")
      (node (ref "H5") (pin "1") (pinfunction "1_1") (pintype "unspecified"))
      (node (ref "J2") (pin "1") (pinfunction "D1/TX_1") (pintype "unspecified"))
    )
    (net (code "19") (name "D2") (class "Default")
      (node (ref "H5") (pin "5") (pinfunction "5_5") (pintype "unspecified"))
      (node (ref "J2") (pin "5") (pinfunction "D2/INT0_5") (pintype "unspecified"))
      (node (ref "SENS_2") (pin "2") (pinfunction "2_2") (pintype "unspecified"))
      (node (ref "SW2") (pin "1") (pinfunction "1_1") (pintype "unspecified"))
      (node (ref "SW2") (pin "2") (pinfunction "2_2") (pintype "unspecified"))
    )
    (net (code "20") (name "D3") (class "Default")
      (node (ref "H5") (pin "6") (pinfunction "6_6") (pintype "unspecified"))
      (node (ref "J2") (pin "6") (pinfunction "D3/INT1_6") (pintype "unspecified"))
      (node (ref "SENS_3") (pin "2") (pinfunction "2_2") (pintype "unspecified"))
      (node (ref "SW3") (pin "1") (pinfunction "1_1") (pintype "unspecified"))
      (node (ref "SW3") (pin "2") (pinfunction "2_2") (pintype "unspecified"))
    )
    (net (code "21") (name "D4") (class "Default")
      (node (ref "ALD") (pin "1") (pinfunction "A_1") (pintype "input"))
      (node (ref "AQ") (pin "1") (pinfunction "G_1") (pintype "unspecified"))
      (node (ref "ARG") (pin "2") (pinfunction "2_2") (pintype "input"))
      (node (ref "H5") (pin "7") (pinfunction "7_7") (pintype "unspecified"))
      (node (ref "J2") (pin "7") (pinfunction "D4/T0_7") (pintype "unspecified"))
      (node (ref "OUT_4") (pin "1") (pinfunction "1_1") (pintype "unspecified"))
    )
    (net (code "22") (name "D5") (class "Default")
      (node (ref "BLD") (pin "1") (pinfunction "A_1") (pintype "input"))
      (node (ref "BQ") (pin "1") (pinfunction "G_1") (pintype "unspecified"))
      (node (ref "BRG") (pin "2") (pinfunction "2_2") (pintype "input"))
      (node (ref "H5") (pin "8") (pinfunction "8_8") (pintype "unspecified"))
      (node (ref "J2") (pin "8") (pinfunction "D5/T1_8") (pintype "unspecified"))
      (node (ref "OUT_5") (pin "1") (pinfunction "1_1") (pintype "unspecified"))
    )
    (net (code "23") (name "D6") (class "Default")
      (node (ref "CLD") (pin "1") (pinfunction "A_1") (pintype "input"))
      (node (ref "CQ") (pin "1") (pinfunction "G_1") (pintype "unspecified"))
      (node (ref "CRG") (pin "2") (pinfunction "2_2") (pintype "input"))
      (node (ref "H5") (pin "9") (pinfunction "9_9") (pintype "unspecified"))
      (node (ref "J2") (pin "9") (pinfunction "D6/AIN0_9") (pintype "unspecified"))
      (node (ref "OUT_6") (pin "1") (pinfunction "1_1") (pintype "unspecified"))
    )
    (net (code "24") (name "D7") (class "Default")
      (node (ref "DLD") (pin "1") (pinfunction "A_1") (pintype "input"))
      (node (ref "DQ") (pin "1") (pinfunction "G_1") (pintype "unspecified"))
      (node (ref "DRG") (pin "2") (pinfunction "2_2") (pintype "input"))
      (node (ref "H5") (pin "10") (pinfunction "10_10") (pintype "unspecified"))
      (node (ref "J2") (pin "10") (pinfunction "D7/AIN1_10") (pintype "unspecified"))
      (node (ref "OUT_7") (pin "1") (pinfunction "1_1") (pintype "unspecified"))
    )
    (net (code "25") (name "D8") (class "Default")
      (node (ref "ELD") (pin "1") (pinfunction "A_1") (pintype "input"))
      (node (ref "EQ") (pin "1") (pinfunction "G_1") (pintype "unspecified"))
      (node (ref "ERG") (pin "2") (pinfunction "2_2") (pintype "input"))
      (node (ref "H5") (pin "11") (pinfunction "11_11") (pintype "unspecified"))
      (node (ref "J2") (pin "11") (pinfunction "D8/ICP_11") (pintype "unspecified"))
      (node (ref "OUT_8") (pin "1") (pinfunction "1_1") (pintype "unspecified"))
    )
    (net (code "26") (name "D9") (class "Default")
      (node (ref "FLD") (pin "1") (pinfunction "A_1") (pintype "input"))
      (node (ref "FQ") (pin "1") (pinfunction "G_1") (pintype "unspecified"))
      (node (ref "FRG") (pin "2") (pinfunction "2_2") (pintype "input"))
      (node (ref "H5") (pin "12") (pinfunction "12_12") (pintype "unspecified"))
      (node (ref "J2") (pin "12") (pinfunction "D9/0C1_12") (pintype "unspecified"))
      (node (ref "OUT_9") (pin "1") (pinfunction "1_1") (pintype "unspecified"))
    )
    (net (code "27") (name "D10") (class "Default")
      (node (ref "GLD") (pin "1") (pinfunction "A_1") (pintype "input"))
      (node (ref "GQ") (pin "1") (pinfunction "G_1") (pintype "unspecified"))
      (node (ref "GRG") (pin "2") (pinfunction "2_2") (pintype "input"))
      (node (ref "H5") (pin "13") (pinfunction "13_13") (pintype "unspecified"))
      (node (ref "J2") (pin "13") (pinfunction "D10_13") (pintype "unspecified"))
      (node (ref "OUT_10") (pin "1") (pinfunction "1_1") (pintype "unspecified"))
    )
    (net (code "28") (name "D11") (class "Default")
      (node (ref "H5") (pin "14") (pinfunction "14_14") (pintype "unspecified"))
      (node (ref "HLD") (pin "1") (pinfunction "A_1") (pintype "input"))
      (node (ref "HQ") (pin "1") (pinfunction "G_1") (pintype "unspecified"))
      (node (ref "HRG") (pin "2") (pinfunction "2_2") (pintype "input"))
      (node (ref "J2") (pin "14") (pinfunction "D11/MOSI_14") (pintype "unspecified"))
      (node (ref "OUT_11") (pin "1") (pinfunction "1_1") (pintype "unspecified"))
    )
    (net (code "29") (name "D13") (class "Default")
      (node (ref "H4") (pin "15") (pinfunction "15_15") (pintype "unspecified"))
      (node (ref "J2") (pin "16") (pinfunction "SCK/D13_16") (pintype "unspecified"))
    )
    (net (code "30") (name "GND") (class "Default")
      (node (ref "AQ") (pin "2") (pinfunction "S_2") (pintype "unspecified"))
      (node (ref "ARG") (pin "1") (pinfunction "1_1") (pintype "input"))
      (node (ref "ARL") (pin "1") (pinfunction "1_1") (pintype "input"))
      (node (ref "BQ") (pin "2") (pinfunction "S_2") (pintype "unspecified"))
      (node (ref "BRG") (pin "1") (pinfunction "1_1") (pintype "input"))
      (node (ref "BRL") (pin "1") (pinfunction "1_1") (pintype "input"))
      (node (ref "BUZZER1") (pin "2") (pinfunction "2_2") (pintype "unspecified"))
      (node (ref "C1") (pin "2") (pinfunction "2_2") (pintype "input"))
      (node (ref "C10") (pin "1") (pinfunction "1_1") (pintype "unspecified"))
      (node (ref "C11") (pin "1") (pinfunction "1_1") (pintype "unspecified"))
      (node (ref "C2") (pin "2") (pinfunction "2_2") (pintype "input"))
      (node (ref "C3") (pin "1") (pinfunction "1_1") (pintype "unspecified"))
      (node (ref "CQ") (pin "2") (pinfunction "S_2") (pintype "unspecified"))
      (node (ref "CRG") (pin "1") (pinfunction "1_1") (pintype "input"))
      (node (ref "CRL") (pin "1") (pinfunction "1_1") (pintype "input"))
      (node (ref "DC1") (pin "2") (pinfunction "2_2") (pintype "unspecified"))
      (node (ref "DC1") (pin "3") (pinfunction "3_3") (pintype "unspecified"))
      (node (ref "DDM1") (pin "2") (pinfunction "A_2") (pintype "unspecified"))
      (node (ref "DQ") (pin "2") (pinfunction "S_2") (pintype "unspecified"))
      (node (ref "DRG") (pin "1") (pinfunction "1_1") (pintype "input"))
      (node (ref "DRL") (pin "1") (pinfunction "1_1") (pintype "input"))
      (node (ref "EQ") (pin "2") (pinfunction "S_2") (pintype "unspecified"))
      (node (ref "ERG") (pin "1") (pinfunction "1_1") (pintype "input"))
      (node (ref "ERL") (pin "1") (pinfunction "1_1") (pintype "input"))
      (node (ref "EX_V") (pin "2") (pinfunction "2_2") (pintype "unspecified"))
      (node (ref "FQ") (pin "2") (pinfunction "S_2") (pintype "unspecified"))
      (node (ref "FRG") (pin "1") (pinfunction "1_1") (pintype "input"))
      (node (ref "FRL") (pin "1") (pinfunction "1_1") (pintype "input"))
      (node (ref "GQ") (pin "2") (pinfunction "S_2") (pintype "unspecified"))
      (node (ref "GRG") (pin "1") (pinfunction "1_1") (pintype "input"))
      (node (ref "GRL") (pin "1") (pinfunction "1_1") (pintype "input"))
      (node (ref "H1") (pin "6") (pinfunction "6_6") (pintype "input"))
      (node (ref "H11") (pin "6") (pinfunction "6_6") (pintype "input"))
      (node (ref "H2") (pin "6") (pinfunction "6_6") (pintype "input"))
      (node (ref "H3") (pin "6") (pinfunction "6_6") (pintype "input"))
      (node (ref "H4") (pin "2") (pinfunction "2_2") (pintype "unspecified"))
      (node (ref "H5") (pin "4") (pinfunction "4_4") (pintype "unspecified"))
      (node (ref "H6") (pin "6") (pinfunction "6_6") (pintype "input"))
      (node (ref "HQ") (pin "2") (pinfunction "S_2") (pintype "unspecified"))
      (node (ref "HRG") (pin "1") (pinfunction "1_1") (pintype "input"))
      (node (ref "HRL") (pin "1") (pinfunction "1_1") (pintype "input"))
      (node (ref "J2") (pin "29") (pinfunction "GND_29") (pintype "unspecified"))
      (node (ref "J2") (pin "4") (pinfunction "GND_4") (pintype "unspecified"))
      (node (ref "OLED") (pin "2") (pinfunction "GND_2") (pintype "passive"))
      (node (ref "OUT_10") (pin "2") (pinfunction "2_2") (pintype "unspecified"))
      (node (ref "OUT_11") (pin "2") (pinfunction "2_2") (pintype "unspecified"))
      (node (ref "OUT_4") (pin "2") (pinfunction "2_2") (pintype "unspecified"))
      (node (ref "OUT_5") (pin "2") (pinfunction "2_2") (pintype "unspecified"))
      (node (ref "OUT_6") (pin "2") (pinfunction "2_2") (pintype "unspecified"))
      (node (ref "OUT_7") (pin "2") (pinfunction "2_2") (pintype "unspecified"))
      (node (ref "OUT_8") (pin "2") (pinfunction "2_2") (pintype "unspecified"))
      (node (ref "OUT_9") (pin "2") (pinfunction "2_2") (pintype "unspecified"))
      (node (ref "P2") (pin "1") (pinfunction "1_1") (pintype "input"))
      (node (ref "P3") (pin "1") (pinfunction "1_1") (pintype "input"))
      (node (ref "RL12V") (pin "2") (pinfunction "2_2") (pintype "input"))
      (node (ref "RL5VB") (pin "2") (pinfunction "2_2") (pintype "input"))
      (node (ref "SENS_2") (pin "3") (pinfunction "3_3") (pintype "unspecified"))
      (node (ref "SENS_3") (pin "3") (pinfunction "3_3") (pintype "unspecified"))
      (node (ref "SENS_A0") (pin "3") (pinfunction "3_3") (pintype "unspecified"))
      (node (ref "SENS_A1") (pin "3") (pinfunction "3_3") (pintype "unspecified"))
      (node (ref "SENS_A2") (pin "3") (pinfunction "3_3") (pintype "unspecified"))
      (node (ref "SENS_A3") (pin "3") (pinfunction "3_3") (pintype "unspecified"))
      (node (ref "SW2") (pin "3") (pinfunction "3_3") (pintype "unspecified"))
      (node (ref "SW2") (pin "4") (pinfunction "4_4") (pintype "unspecified"))
      (node (ref "SW3") (pin "3") (pinfunction "3_3") (pintype "unspecified"))
      (node (ref "SW3") (pin "4") (pinfunction "4_4") (pintype "unspecified"))
      (node (ref "SWA0") (pin "3") (pinfunction "3_3") (pintype "unspecified"))
      (node (ref "SWA0") (pin "4") (pinfunction "4_4") (pintype "unspecified"))
      (node (ref "SWA1") (pin "3") (pinfunction "3_3") (pintype "unspecified"))
      (node (ref "SWA1") (pin "4") (pinfunction "4_4") (pintype "unspecified"))
      (node (ref "SWA2") (pin "3") (pinfunction "3_3") (pintype "unspecified"))
      (node (ref "SWA2") (pin "4") (pinfunction "4_4") (pintype "unspecified"))
      (node (ref "SWA3") (pin "3") (pinfunction "3_3") (pintype "unspecified"))
      (node (ref "SWA3") (pin "4") (pinfunction "4_4") (pintype "unspecified"))
      (node (ref "U2") (pin "5") (pinfunction "GND_5") (pintype "unspecified"))
      (node (ref "U3") (pin "3") (pinfunction "GND_3") (pintype "unspecified"))
      (node (ref "U5") (pin "2") (pinfunction "GND_2") (pintype "unspecified"))
      (node (ref "VALVE-CON") (pin "2") (pinfunction "2_2") (pintype "unspecified"))
    )
    (net (code "31") (name "Net-(ADM-A)") (class "Default")
      (node (ref "ACM") (pin "2") (pinfunction "2_2") (pintype "input"))
      (node (ref "ACON") (pin "2") (pinfunction "2_2") (pintype "unspecified"))
      (node (ref "ADM") (pin "2") (pinfunction "A_2") (pintype "unspecified"))
      (node (ref "AQ") (pin "3") (pinfunction "D_3") (pintype "unspecified"))
    )
    (net (code "32") (name "Net-(ADM-C)") (class "Default")
      (node (ref "ACM") (pin "1") (pinfunction "1_1") (pintype "input"))
      (node (ref "ACON") (pin "1") (pinfunction "1_1") (pintype "unspecified"))
      (node (ref "ADM") (pin "1") (pinfunction "C_1") (pintype "unspecified"))
      (node (ref "AJ12V") (pin "1") (pinfunction "1_1") (pintype "bidirectional"))
      (node (ref "AJ5V") (pin "1") (pinfunction "1_1") (pintype "bidirectional"))
    )
    (net (code "33") (name "Net-(ALD-C)") (class "Default")
      (node (ref "ALD") (pin "2") (pinfunction "C_2") (pintype "input"))
      (node (ref "ARL") (pin "2") (pinfunction "2_2") (pintype "input"))
    )
    (net (code "34") (name "Net-(BDM-A)") (class "Default")
      (node (ref "BCM") (pin "2") (pinfunction "2_2") (pintype "input"))
      (node (ref "BCON") (pin "2") (pinfunction "2_2") (pintype "unspecified"))
      (node (ref "BDM") (pin "2") (pinfunction "A_2") (pintype "unspecified"))
      (node (ref "BQ") (pin "3") (pinfunction "D_3") (pintype "unspecified"))
    )
    (net (code "35") (name "Net-(BDM-C)") (class "Default")
      (node (ref "BCM") (pin "1") (pinfunction "1_1") (pintype "input"))
      (node (ref "BCON") (pin "1") (pinfunction "1_1") (pintype "unspecified"))
      (node (ref "BDM") (pin "1") (pinfunction "C_1") (pintype "unspecified"))
      (node (ref "BJ12V") (pin "1") (pinfunction "1_1") (pintype "bidirectional"))
      (node (ref "BJ5V") (pin "1") (pinfunction "1_1") (pintype "bidirectional"))
    )
    (net (code "36") (name "Net-(BLD-C)") (class "Default")
      (node (ref "BLD") (pin "2") (pinfunction "C_2") (pintype "input"))
      (node (ref "BRL") (pin "2") (pinfunction "2_2") (pintype "input"))
    )
    (net (code "37") (name "Net-(CDM-A)") (class "Default")
      (node (ref "CCM") (pin "2") (pinfunction "2_2") (pintype "input"))
      (node (ref "CCON") (pin "2") (pinfunction "2_2") (pintype "unspecified"))
      (node (ref "CDM") (pin "2") (pinfunction "A_2") (pintype "unspecified"))
      (node (ref "CQ") (pin "3") (pinfunction "D_3") (pintype "unspecified"))
    )
    (net (code "38") (name "Net-(CDM-C)") (class "Default")
      (node (ref "CCM") (pin "1") (pinfunction "1_1") (pintype "input"))
      (node (ref "CCON") (pin "1") (pinfunction "1_1") (pintype "unspecified"))
      (node (ref "CDM") (pin "1") (pinfunction "C_1") (pintype "unspecified"))
      (node (ref "CJ12V") (pin "1") (pinfunction "1_1") (pintype "bidirectional"))
      (node (ref "CJ5V") (pin "1") (pinfunction "1_1") (pintype "bidirectional"))
    )
    (net (code "39") (name "Net-(CLD-C)") (class "Default")
      (node (ref "CLD") (pin "2") (pinfunction "C_2") (pintype "input"))
      (node (ref "CRL") (pin "2") (pinfunction "2_2") (pintype "input"))
    )
    (net (code "40") (name "Net-(D1-A)") (class "Default")
      (node (ref "D1") (pin "2") (pinfunction "A_2") (pintype "unspecified"))
      (node (ref "RLY1") (pin "4") (pinfunction "4_4") (pintype "unspecified"))
    )
    (net (code "41") (name "Net-(D7-A)") (class "Default")
      (node (ref "D7") (pin "2") (pinfunction "A_2") (pintype "unspecified"))
      (node (ref "RLY4") (pin "4") (pinfunction "4_4") (pintype "unspecified"))
    )
    (net (code "42") (name "Net-(DDM-A)") (class "Default")
      (node (ref "DCM") (pin "2") (pinfunction "2_2") (pintype "input"))
      (node (ref "DCON") (pin "2") (pinfunction "2_2") (pintype "unspecified"))
      (node (ref "DDM") (pin "2") (pinfunction "A_2") (pintype "unspecified"))
      (node (ref "DQ") (pin "3") (pinfunction "D_3") (pintype "unspecified"))
    )
    (net (code "43") (name "Net-(DDM-C)") (class "Default")
      (node (ref "DCM") (pin "1") (pinfunction "1_1") (pintype "input"))
      (node (ref "DCON") (pin "1") (pinfunction "1_1") (pintype "unspecified"))
      (node (ref "DDM") (pin "1") (pinfunction "C_1") (pintype "unspecified"))
      (node (ref "DJ12V") (pin "1") (pinfunction "1_1") (pintype "bidirectional"))
      (node (ref "DJ5V") (pin "1") (pinfunction "1_1") (pintype "bidirectional"))
    )
    (net (code "44") (name "Net-(DDM1-C)") (class "Default")
      (node (ref "DDM1") (pin "1") (pinfunction "C_1") (pintype "unspecified"))
      (node (ref "RLY4") (pin "2") (pinfunction "2_2") (pintype "unspecified"))
      (node (ref "VALVE-CON") (pin "1") (pinfunction "1_1") (pintype "unspecified"))
    )
    (net (code "45") (name "Net-(DDM2-A)") (class "Default")
      (node (ref "DDM2") (pin "2") (pinfunction "A_2") (pintype "unspecified"))
      (node (ref "IGNIT_CON") (pin "2") (pinfunction "2_2") (pintype "unspecified"))
    )
    (net (code "46") (name "Net-(DDM2-C)") (class "Default")
      (node (ref "DDM2") (pin "1") (pinfunction "C_1") (pintype "unspecified"))
      (node (ref "IGNIT_CON") (pin "1") (pinfunction "1_1") (pintype "unspecified"))
      (node (ref "RLY4") (pin "1") (pinfunction "1_1") (pintype "unspecified"))
    )
    (net (code "47") (name "Net-(DLD-C)") (class "Default")
      (node (ref "DLD") (pin "2") (pinfunction "C_2") (pintype "input"))
      (node (ref "DRL") (pin "2") (pinfunction "2_2") (pintype "input"))
    )
    (net (code "48") (name "Net-(EDM-A)") (class "Default")
      (node (ref "ECM") (pin "2") (pinfunction "2_2") (pintype "input"))
      (node (ref "ECON") (pin "2") (pinfunction "2_2") (pintype "unspecified"))
      (node (ref "EDM") (pin "2") (pinfunction "A_2") (pintype "unspecified"))
      (node (ref "EQ") (pin "3") (pinfunction "D_3") (pintype "unspecified"))
    )
    (net (code "49") (name "Net-(EDM-C)") (class "Default")
      (node (ref "ECM") (pin "1") (pinfunction "1_1") (pintype "input"))
      (node (ref "ECON") (pin "1") (pinfunction "1_1") (pintype "unspecified"))
      (node (ref "EDM") (pin "1") (pinfunction "C_1") (pintype "unspecified"))
      (node (ref "EJ12V") (pin "1") (pinfunction "1_1") (pintype "bidirectional"))
      (node (ref "EJ5V") (pin "1") (pinfunction "1_1") (pintype "bidirectional"))
    )
    (net (code "50") (name "Net-(ELD-C)") (class "Default")
      (node (ref "ELD") (pin "2") (pinfunction "C_2") (pintype "input"))
      (node (ref "ERL") (pin "2") (pinfunction "2_2") (pintype "input"))
    )
    (net (code "51") (name "Net-(FDM-A)") (class "Default")
      (node (ref "FCM") (pin "2") (pinfunction "2_2") (pintype "input"))
      (node (ref "FCON") (pin "2") (pinfunction "2_2") (pintype "unspecified"))
      (node (ref "FDM") (pin "2") (pinfunction "A_2") (pintype "unspecified"))
      (node (ref "FQ") (pin "3") (pinfunction "D_3") (pintype "unspecified"))
    )
    (net (code "52") (name "Net-(FDM-C)") (class "Default")
      (node (ref "FCM") (pin "1") (pinfunction "1_1") (pintype "input"))
      (node (ref "FCON") (pin "1") (pinfunction "1_1") (pintype "unspecified"))
      (node (ref "FDM") (pin "1") (pinfunction "C_1") (pintype "unspecified"))
      (node (ref "FJ12V") (pin "1") (pinfunction "1_1") (pintype "bidirectional"))
      (node (ref "FJ5V") (pin "1") (pinfunction "1_1") (pintype "bidirectional"))
    )
    (net (code "53") (name "Net-(FLD-C)") (class "Default")
      (node (ref "FLD") (pin "2") (pinfunction "C_2") (pintype "input"))
      (node (ref "FRL") (pin "2") (pinfunction "2_2") (pintype "input"))
    )
    (net (code "54") (name "Net-(GDM-A)") (class "Default")
      (node (ref "GCM") (pin "2") (pinfunction "2_2") (pintype "input"))
      (node (ref "GCON") (pin "2") (pinfunction "2_2") (pintype "unspecified"))
      (node (ref "GDM") (pin "2") (pinfunction "A_2") (pintype "unspecified"))
      (node (ref "GQ") (pin "3") (pinfunction "D_3") (pintype "unspecified"))
    )
    (net (code "55") (name "Net-(GDM-C)") (class "Default")
      (node (ref "GCM") (pin "1") (pinfunction "1_1") (pintype "input"))
      (node (ref "GCON") (pin "1") (pinfunction "1_1") (pintype "unspecified"))
      (node (ref "GDM") (pin "1") (pinfunction "C_1") (pintype "unspecified"))
      (node (ref "GJ12V") (pin "1") (pinfunction "1_1") (pintype "bidirectional"))
      (node (ref "GJ5V") (pin "1") (pinfunction "1_1") (pintype "bidirectional"))
    )
    (net (code "56") (name "Net-(GLD-C)") (class "Default")
      (node (ref "GLD") (pin "2") (pinfunction "C_2") (pintype "input"))
      (node (ref "GRL") (pin "2") (pinfunction "2_2") (pintype "input"))
    )
    (net (code "57") (name "Net-(H4-Pad3)") (class "Default")
      (node (ref "H4") (pin "3") (pinfunction "3_3") (pintype "unspecified"))
      (node (ref "J2") (pin "28") (pinfunction "RESET_28") (pintype "unspecified"))
    )
    (net (code "58") (name "Net-(H5-Pad3)") (class "Default")
      (node (ref "H5") (pin "3") (pinfunction "3_3") (pintype "unspecified"))
      (node (ref "J2") (pin "3") (pinfunction "RESET_3") (pintype "unspecified"))
    )
    (net (code "59") (name "Net-(HDM-A)") (class "Default")
      (node (ref "HCM") (pin "2") (pinfunction "2_2") (pintype "input"))
      (node (ref "HCON") (pin "2") (pinfunction "2_2") (pintype "unspecified"))
      (node (ref "HDM") (pin "2") (pinfunction "A_2") (pintype "unspecified"))
      (node (ref "HQ") (pin "3") (pinfunction "D_3") (pintype "unspecified"))
    )
    (net (code "60") (name "Net-(HDM-C)") (class "Default")
      (node (ref "HCM") (pin "1") (pinfunction "1_1") (pintype "input"))
      (node (ref "HCON") (pin "1") (pinfunction "1_1") (pintype "unspecified"))
      (node (ref "HDM") (pin "1") (pinfunction "C_1") (pintype "unspecified"))
      (node (ref "HJ12V") (pin "1") (pinfunction "1_1") (pintype "bidirectional"))
      (node (ref "HJ5V") (pin "1") (pinfunction "1_1") (pintype "bidirectional"))
    )
    (net (code "61") (name "Net-(HLD-C)") (class "Default")
      (node (ref "HLD") (pin "2") (pinfunction "C_2") (pintype "input"))
      (node (ref "HRL") (pin "2") (pinfunction "2_2") (pintype "input"))
    )
    (net (code "62") (name "Net-(J2-AREF)") (class "Default")
      (node (ref "H4") (pin "13") (pinfunction "13_13") (pintype "unspecified"))
      (node (ref "J2") (pin "18") (pinfunction "AREF_18") (pintype "unspecified"))
    )
    (net (code "63") (name "Net-(L12V-C)") (class "Default")
      (node (ref "L12V") (pin "2") (pinfunction "C_2") (pintype "input"))
      (node (ref "RL12V") (pin "1") (pinfunction "1_1") (pintype "input"))
    )
    (net (code "64") (name "Net-(LVB-C)") (class "Default")
      (node (ref "LVB") (pin "2") (pinfunction "C_2") (pintype "input"))
      (node (ref "RL5VB") (pin "1") (pinfunction "1_1") (pintype "input"))
    )
    (net (code "65") (name "Net-(RLY1-Pad5)") (class "Default")
      (node (ref "RLY1") (pin "5") (pinfunction "5_5") (pintype "unspecified"))
      (node (ref "U2") (pin "1") (pinfunction "IP+_1") (pintype "unspecified"))
      (node (ref "U2") (pin "2") (pinfunction "IP+_2") (pintype "unspecified"))
    )
    (net (code "66") (name "Net-(U2-FILTER)") (class "Default")
      (node (ref "C3") (pin "2") (pinfunction "2_2") (pintype "unspecified"))
      (node (ref "U2") (pin "6") (pinfunction "FILTER_6") (pintype "unspecified"))
    )
    (net (code "67") (name "Net-(U2-IP--Pad3)") (class "Default")
      (node (ref "U2") (pin "3") (pinfunction "IP-_3") (pintype "unspecified"))
      (node (ref "U2") (pin "4") (pinfunction "IP-_4") (pintype "unspecified"))
      (node (ref "XT_M") (pin "2") (pinfunction "2_2") (pintype "unspecified"))
    )
    (net (code "68") (name "Net-(U3-EN)") (class "Default")
      (node (ref "R1") (pin "1") (pinfunction "1_1") (pintype "input"))
      (node (ref "U3") (pin "1") (pinfunction "EN_1") (pintype "unspecified"))
    )
    (net (code "69") (name "Net-(XT_F-+)") (class "Default")
      (node (ref "RLY1") (pin "1") (pinfunction "1_1") (pintype "unspecified"))
      (node (ref "XT_F") (pin "2") (pinfunction "+_2") (pintype "unspecified"))
    )
    (net (code "70") (name "Net-(XT_F--)") (class "Default")
      (node (ref "XT_F") (pin "1") (pinfunction "-_1") (pintype "unspecified"))
      (node (ref "XT_M") (pin "1") (pinfunction "1_1") (pintype "unspecified"))
    )
    (net (code "72") (name "unconnected-(H1-Pad2)") (class "Default")
      (node (ref "H1") (pin "2") (pinfunction "2_2") (pintype "input"))
    )
    (net (code "73") (name "unconnected-(H1-Pad3)") (class "Default")
      (node (ref "H1") (pin "3") (pinfunction "3_3") (pintype "input"))
    )
    (net (code "74") (name "unconnected-(H1-Pad4)") (class "Default")
      (node (ref "H1") (pin "4") (pinfunction "4_4") (pintype "input"))
    )
    (net (code "75") (name "unconnected-(H1-Pad5)") (class "Default")
      (node (ref "H1") (pin "5") (pinfunction "5_5") (pintype "input"))
    )
    (net (code "76") (name "unconnected-(H2-Pad2)") (class "Default")
      (node (ref "H2") (pin "2") (pinfunction "2_2") (pintype "input"))
    )
    (net (code "77") (name "unconnected-(H2-Pad3)") (class "Default")
      (node (ref "H2") (pin "3") (pinfunction "3_3") (pintype "input"))
    )
    (net (code "78") (name "unconnected-(H2-Pad4)") (class "Default")
      (node (ref "H2") (pin "4") (pinfunction "4_4") (pintype "input"))
    )
    (net (code "79") (name "unconnected-(H2-Pad5)") (class "Default")
      (node (ref "H2") (pin "5") (pinfunction "5_5") (pintype "input"))
    )
    (net (code "80") (name "unconnected-(H3-Pad2)") (class "Default")
      (node (ref "H3") (pin "2") (pinfunction "2_2") (pintype "input"))
    )
    (net (code "81") (name "unconnected-(H3-Pad3)") (class "Default")
      (node (ref "H3") (pin "3") (pinfunction "3_3") (pintype "input"))
    )
    (net (code "82") (name "unconnected-(H3-Pad4)") (class "Default")
      (node (ref "H3") (pin "4") (pinfunction "4_4") (pintype "input"))
    )
    (net (code "83") (name "unconnected-(H3-Pad5)") (class "Default")
      (node (ref "H3") (pin "5") (pinfunction "5_5") (pintype "input"))
    )
    (net (code "84") (name "unconnected-(H6-Pad2)") (class "Default")
      (node (ref "H6") (pin "2") (pinfunction "2_2") (pintype "input"))
    )
    (net (code "85") (name "unconnected-(H6-Pad3)") (class "Default")
      (node (ref "H6") (pin "3") (pinfunction "3_3") (pintype "input"))
    )
    (net (code "86") (name "unconnected-(H6-Pad4)") (class "Default")
      (node (ref "H6") (pin "4") (pinfunction "4_4") (pintype "input"))
    )
    (net (code "87") (name "unconnected-(H6-Pad5)") (class "Default")
      (node (ref "H6") (pin "5") (pinfunction "5_5") (pintype "input"))
    )
    (net (code "88") (name "unconnected-(H11-Pad2)") (class "Default")
      (node (ref "H11") (pin "2") (pinfunction "2_2") (pintype "input"))
    )
    (net (code "89") (name "unconnected-(H11-Pad3)") (class "Default")
      (node (ref "H11") (pin "3") (pinfunction "3_3") (pintype "input"))
    )
    (net (code "90") (name "unconnected-(H11-Pad4)") (class "Default")
      (node (ref "H11") (pin "4") (pinfunction "4_4") (pintype "input"))
    )
    (net (code "91") (name "unconnected-(H11-Pad5)") (class "Default")
      (node (ref "H11") (pin "5") (pinfunction "5_5") (pintype "input"))
    )
    (net (code "92") (name "unconnected-(P2-Pad4)") (class "Default")
      (node (ref "P2") (pin "4") (pinfunction "4_4") (pintype "input"))
    )
    (net (code "93") (name "unconnected-(P2-Pad5)") (class "Default")
      (node (ref "P2") (pin "5") (pinfunction "5_5") (pintype "input"))
    )
    (net (code "94") (name "unconnected-(P3-Pad4)") (class "Default")
      (node (ref "P3") (pin "4") (pinfunction "4_4") (pintype "input"))
    )
    (net (code "95") (name "unconnected-(P3-Pad5)") (class "Default")
      (node (ref "P3") (pin "5") (pinfunction "5_5") (pintype "input"))
    )
    (net (code "96") (name "unconnected-(RLY1-Pad2)") (class "Default")
      (node (ref "RLY1") (pin "2") (pinfunction "2_2") (pintype "unspecified"))
    )
    (net (code "97") (name "unconnected-(U1-Pad1)") (class "Default")
      (node (ref "U1") (pin "1") (pinfunction "1_1") (pintype "unspecified"))
    )
    (net (code "98") (name "unconnected-(U1-Pad2)") (class "Default")
      (node (ref "U1") (pin "2") (pinfunction "2_2") (pintype "unspecified"))
    )
    (net (code "99") (name "unconnected-(U1-Pad3)") (class "Default")
      (node (ref "U1") (pin "3") (pinfunction "3_3") (pintype "unspecified"))
    )
    (net (code "100") (name "unconnected-(U1-Pad4)") (class "Default")
      (node (ref "U1") (pin "4") (pinfunction "4_4") (pintype "unspecified"))
    )
    (net (code "101") (name "unconnected-(U2-VIOUT-Pad7)") (class "Default")
      (node (ref "U2") (pin "7") (pinfunction "VIOUT_7") (pintype "unspecified"))
    )
    (net (code "102") (name "unconnected-(U4-Pad1)") (class "Default")
      (node (ref "U4") (pin "1") (pinfunction "1_1") (pintype "unspecified"))
    )
    (net (code "103") (name "unconnected-(U4-Pad2)") (class "Default")
      (node (ref "U4") (pin "2") (pinfunction "2_2") (pintype "unspecified"))
    )
  )
)
